# TJA1051T.net
KiCad netlist of a schematic drawn in Altium Designer
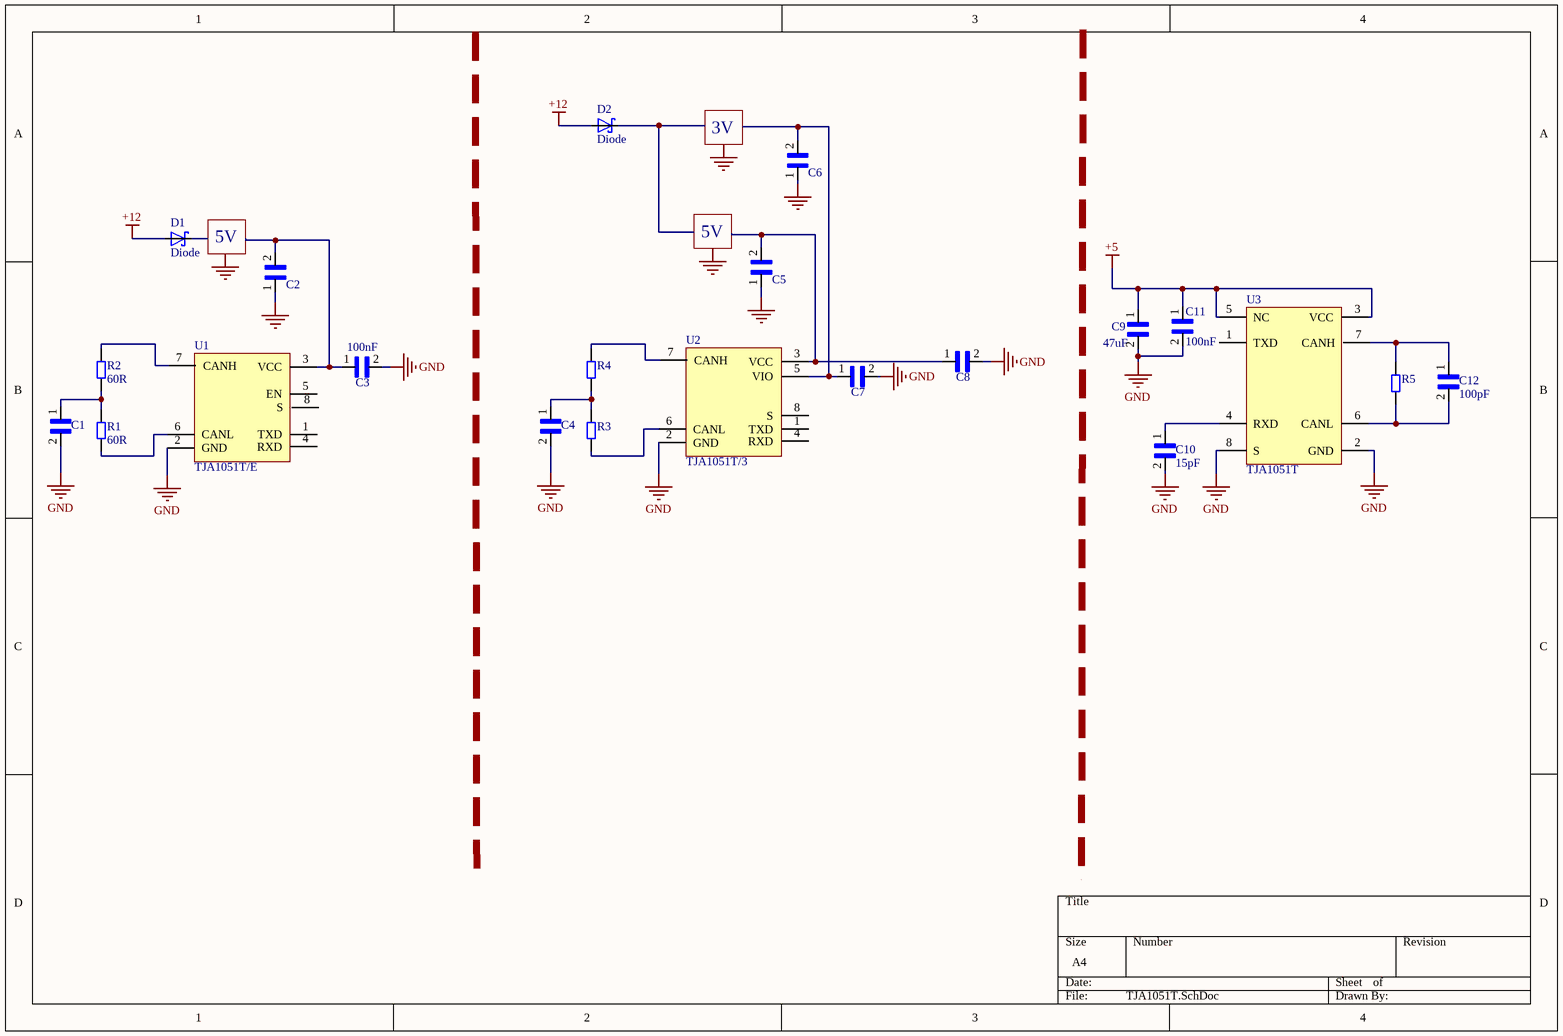
[diagram p0: TJA1051T.SchDoc]

(export (version "E")
  (design (tool "Eeschema 10.0.6"))
  (components
    (comp (ref "C1")
      (value "CAP-0805-NP0-10nF")
      (footprint "CAP-0805-NP0")
      (description "Cap Ceramic 0.01uF 50V C0G 5% Pad SMD 0805 125°C T/R")
      (fields
        (field (name "MANUFACTURER") "Yageo")
        (field (name "MANUFACTURER PART NUMBER") "CC0805JKNPO9BN103")
      )
      (libsource (lib "") (part "CAP-0805-NP0-10nF_1"))
    )
    (comp (ref "C2")
      (value "CAP-0805-NP0-10nF")
      (footprint "CAP-0805-NP0")
      (description "Cap Ceramic 0.01uF 50V C0G 5% Pad SMD 0805 125°C T/R")
      (fields
        (field (name "MANUFACTURER") "Yageo")
        (field (name "MANUFACTURER PART NUMBER") "CC0805JKNPO9BN103")
      )
      (libsource (lib "") (part "CAP-0805-NP0-10nF_2"))
    )
    (comp (ref "C3")
      (value "100nF")
      (footprint "CAP-0805-NP0")
      (description "Cap Ceramic 0.01uF 50V C0G 5% Pad SMD 0805 125°C T/R")
      (fields
        (field (name "MANUFACTURER") "Yageo")
        (field (name "MANUFACTURER PART NUMBER") "CC0805JKNPO9BN103")
      )
      (libsource (lib "Schlib2") (part "CAP-0805-NP0-10nF"))
    )
    (comp (ref "C4")
      (value "CAP-0805-NP0-10nF")
      (footprint "CAP-0805-NP0")
      (description "Cap Ceramic 0.01uF 50V C0G 5% Pad SMD 0805 125°C T/R")
      (fields
        (field (name "MANUFACTURER") "Yageo")
        (field (name "MANUFACTURER PART NUMBER") "CC0805JKNPO9BN103")
      )
      (libsource (lib "") (part "CAP-0805-NP0-10nF_1"))
    )
    (comp (ref "C5")
      (value "CAP-0805-NP0-10nF")
      (footprint "CAP-0805-NP0")
      (description "Cap Ceramic 0.01uF 50V C0G 5% Pad SMD 0805 125°C T/R")
      (fields
        (field (name "MANUFACTURER") "Yageo")
        (field (name "MANUFACTURER PART NUMBER") "CC0805JKNPO9BN103")
      )
      (libsource (lib "") (part "CAP-0805-NP0-10nF_2"))
    )
    (comp (ref "C6")
      (value "CAP-0805-NP0-10nF")
      (footprint "CAP-0805-NP0")
      (description "Cap Ceramic 0.01uF 50V C0G 5% Pad SMD 0805 125°C T/R")
      (fields
        (field (name "MANUFACTURER") "Yageo")
        (field (name "MANUFACTURER PART NUMBER") "CC0805JKNPO9BN103")
      )
      (libsource (lib "") (part "CAP-0805-NP0-10nF_2"))
    )
    (comp (ref "C7")
      (value "CAP-0805-NP0-10nF")
      (footprint "CAP-0805-NP0")
      (description "Cap Ceramic 0.01uF 50V C0G 5% Pad SMD 0805 125°C T/R")
      (fields
        (field (name "MANUFACTURER") "Yageo")
        (field (name "MANUFACTURER PART NUMBER") "CC0805JKNPO9BN103")
      )
      (libsource (lib "Schlib2") (part "CAP-0805-NP0-10nF"))
    )
    (comp (ref "C8")
      (value "CAP-0805-NP0-10nF")
      (footprint "CAP-0805-NP0")
      (description "Cap Ceramic 0.01uF 50V C0G 5% Pad SMD 0805 125°C T/R")
      (fields
        (field (name "MANUFACTURER") "Yageo")
        (field (name "MANUFACTURER PART NUMBER") "CC0805JKNPO9BN103")
      )
      (libsource (lib "Schlib2") (part "CAP-0805-NP0-10nF"))
    )
    (comp (ref "C9")
      (value "47uF")
      (footprint "CAP-0805-NP0")
      (description "Cap Ceramic 0.01uF 50V C0G 5% Pad SMD 0805 125°C T/R")
      (fields
        (field (name "MANUFACTURER") "Yageo")
        (field (name "MANUFACTURER PART NUMBER") "CC0805JKNPO9BN103")
      )
      (libsource (lib "") (part "CAP-0805-NP0-10nF_1"))
    )
    (comp (ref "C10")
      (value "15pF")
      (footprint "CAP-0805-NP0")
      (description "Cap Ceramic 0.01uF 50V C0G 5% Pad SMD 0805 125°C T/R")
      (fields
        (field (name "MANUFACTURER") "Yageo")
        (field (name "MANUFACTURER PART NUMBER") "CC0805JKNPO9BN103")
      )
      (libsource (lib "") (part "CAP-0805-NP0-10nF_1"))
    )
    (comp (ref "C11")
      (value "100nF")
      (footprint "CAP-0805-NP0")
      (description "Cap Ceramic 0.01uF 50V C0G 5% Pad SMD 0805 125°C T/R")
      (fields
        (field (name "MANUFACTURER") "Yageo")
        (field (name "MANUFACTURER PART NUMBER") "CC0805JKNPO9BN103")
      )
      (libsource (lib "") (part "CAP-0805-NP0-10nF_1"))
    )
    (comp (ref "C12")
      (value "100pF")
      (footprint "CAP-0805-NP0")
      (description "Cap Ceramic 0.01uF 50V C0G 5% Pad SMD 0805 125°C T/R")
      (fields
        (field (name "MANUFACTURER") "Yageo")
        (field (name "MANUFACTURER PART NUMBER") "CC0805JKNPO9BN103")
      )
      (libsource (lib "") (part "CAP-0805-NP0-10nF_1"))
    )
    (comp (ref "D1") (value "Diode") (footprint "Diode") (libsource (lib "Schlib1") (part "Diode")))
    (comp (ref "D2") (value "Diode") (footprint "Diode") (libsource (lib "") (part "Diode_1")))
    (comp (ref "R1")
      (value "60R")
      (footprint "RES-0805")
      (description "Res SMD 0805 10K 1% 0.125W T.C.100PPM")
      (fields
        (field (name "MANUFACTURER") "Yageo")
        (field (name "MANUFACTURER PART NUMBER") "RC0805FR-0710KL")
      )
      (libsource (lib "Schlib2") (part "RES-0805-10k"))
    )
    (comp (ref "R2")
      (value "60R")
      (footprint "RES-0805")
      (description "Res SMD 0805 10K 1% 0.125W T.C.100PPM")
      (fields
        (field (name "MANUFACTURER") "Yageo")
        (field (name "MANUFACTURER PART NUMBER") "RC0805FR-0710KL")
      )
      (libsource (lib "Schlib2") (part "RES-0805-10k"))
    )
    (comp (ref "R3")
      (value "RES-0805-10k")
      (footprint "RES-0805")
      (description "Res SMD 0805 10K 1% 0.125W T.C.100PPM")
      (fields
        (field (name "MANUFACTURER") "Yageo")
        (field (name "MANUFACTURER PART NUMBER") "RC0805FR-0710KL")
      )
      (libsource (lib "Schlib2") (part "RES-0805-10k"))
    )
    (comp (ref "R4")
      (value "RES-0805-10k")
      (footprint "RES-0805")
      (description "Res SMD 0805 10K 1% 0.125W T.C.100PPM")
      (fields
        (field (name "MANUFACTURER") "Yageo")
        (field (name "MANUFACTURER PART NUMBER") "RC0805FR-0710KL")
      )
      (libsource (lib "Schlib2") (part "RES-0805-10k"))
    )
    (comp (ref "R5")
      (value "120R")
      (footprint "RES-0805")
      (description "Res SMD 0805 10K 1% 0.125W T.C.100PPM")
      (fields
        (field (name "MANUFACTURER") "Yageo")
        (field (name "MANUFACTURER PART NUMBER") "RC0805FR-0710KL")
      )
      (libsource (lib "Schlib2") (part "RES-0805-10k"))
    )
    (comp (ref "U1")
      (value "TJA1051T/E")
      (footprint "TJA1051T")
      (description "TJA1051 Series 5.5 V Surface Mount High-Speed CAN Transceiver - SOIC-8")
      (fields
        (field (name "MANUFACTURER") "NXP Semiconductors")
        (field (name "MANUFACTURER PART NUMBER") "TJA1051T/E,118")
      )
      (libsource (lib "Schlib1") (part "TJA1051T/E"))
    )
    (comp (ref "U2")
      (value "TJA1051T/3")
      (footprint "TJA1051T")
      (description "TJA1051 Single 5 V 1 MBd Surface Mount High Speed CAN Transceiver - HVSON-8")
      (fields
        (field (name "MANUFACTURER") "NXP Semiconductors")
        (field (name "MANUFACTURER PART NUMBER") "TJA1051TK/3/1J")
      )
      (libsource (lib "Schlib2") (part "TJA1051T/3"))
    )
    (comp (ref "U3")
      (value "TJA1051T")
      (footprint "TJA1051T")
      (description "CAN 1Mbps Normal/Silent 5V 8-Pin SO Tube")
      (fields (field (name "MANUFACTURER") "NXP Semiconductors"))
      (libsource (lib "Schlib2") (part "TJA1051T"))
    )
  )
  (nets
    (net (code "1") (name "+5") (class "Default")
      (node (ref "C11") (pin "1") (pinfunction "1_1") (pintype "passive"))
      (node (ref "C9") (pin "1") (pinfunction "1_1") (pintype "passive"))
      (node (ref "U3") (pin "3") (pinfunction "VCC_3") (pintype "passive"))
      (node (ref "U3") (pin "5") (pinfunction "NC_5") (pintype "power_in"))
    )
    (net (code "2") (name "+12") (class "Default")
      (node (ref "D1") (pin "1") (pintype "passive"))
      (node (ref "D2") (pin "2") (pintype "passive"))
    )
    (net (code "3") (name "GND") (class "Default")
      (node (ref "C1") (pin "2") (pinfunction "2_2") (pintype "passive"))
      (node (ref "C10") (pin "2") (pinfunction "2_2") (pintype "passive"))
      (node (ref "C11") (pin "2") (pinfunction "2_2") (pintype "passive"))
      (node (ref "C2") (pin "1") (pinfunction "1_1") (pintype "passive"))
      (node (ref "C3") (pin "2") (pinfunction "2_2") (pintype "passive"))
      (node (ref "C4") (pin "2") (pinfunction "2_2") (pintype "passive"))
      (node (ref "C5") (pin "1") (pinfunction "1_1") (pintype "passive"))
      (node (ref "C6") (pin "1") (pinfunction "1_1") (pintype "passive"))
      (node (ref "C7") (pin "2") (pinfunction "2_2") (pintype "passive"))
      (node (ref "C8") (pin "2") (pinfunction "2_2") (pintype "passive"))
      (node (ref "C9") (pin "2") (pinfunction "2_2") (pintype "passive"))
      (node (ref "U1") (pin "2") (pinfunction "GND_2") (pintype "passive"))
      (node (ref "U2") (pin "2") (pinfunction "GND_2") (pintype "passive"))
      (node (ref "U3") (pin "2") (pinfunction "GND_2") (pintype "passive"))
      (node (ref "U3") (pin "8") (pinfunction "S_8") (pintype "passive"))
    )
    (net (code "4") (name "Net-(C1-Pad1)") (class "Default")
      (node (ref "C1") (pin "1") (pinfunction "1_1") (pintype "passive"))
      (node (ref "R1") (pin "2") (pinfunction "2_2") (pintype "passive"))
      (node (ref "R2") (pin "1") (pinfunction "1_1") (pintype "passive"))
    )
    (net (code "5") (name "Net-(C4-Pad1)") (class "Default")
      (node (ref "C4") (pin "1") (pinfunction "1_1") (pintype "passive"))
      (node (ref "R3") (pin "2") (pinfunction "2_2") (pintype "passive"))
      (node (ref "R4") (pin "1") (pinfunction "1_1") (pintype "passive"))
    )
    (net (code "6") (name "Net-(U1-CANH)") (class "Default")
      (node (ref "R2") (pin "2") (pinfunction "2_2") (pintype "passive"))
      (node (ref "U1") (pin "7") (pinfunction "CANH_7") (pintype "passive"))
    )
    (net (code "7") (name "Net-(U1-CANL)") (class "Default")
      (node (ref "R1") (pin "1") (pinfunction "1_1") (pintype "passive"))
      (node (ref "U1") (pin "6") (pinfunction "CANL_6") (pintype "passive"))
    )
    (net (code "8") (name "Net-(U1-VCC)") (class "Default")
      (node (ref "C2") (pin "2") (pinfunction "2_2") (pintype "passive"))
      (node (ref "C3") (pin "1") (pinfunction "1_1") (pintype "passive"))
      (node (ref "U1") (pin "3") (pinfunction "VCC_3") (pintype "passive"))
    )
    (net (code "9") (name "Net-(U2-CANH)") (class "Default")
      (node (ref "R4") (pin "2") (pinfunction "2_2") (pintype "passive"))
      (node (ref "U2") (pin "7") (pinfunction "CANH_7") (pintype "passive"))
    )
    (net (code "10") (name "Net-(U2-CANL)") (class "Default")
      (node (ref "R3") (pin "1") (pinfunction "1_1") (pintype "passive"))
      (node (ref "U2") (pin "6") (pinfunction "CANL_6") (pintype "passive"))
    )
    (net (code "11") (name "Net-(U2-VCC)") (class "Default")
      (node (ref "C5") (pin "2") (pinfunction "2_2") (pintype "passive"))
      (node (ref "C8") (pin "1") (pinfunction "1_1") (pintype "passive"))
      (node (ref "U2") (pin "3") (pinfunction "VCC_3") (pintype "passive"))
    )
    (net (code "12") (name "Net-(U2-VIO)") (class "Default")
      (node (ref "C6") (pin "2") (pinfunction "2_2") (pintype "passive"))
      (node (ref "C7") (pin "1") (pinfunction "1_1") (pintype "passive"))
      (node (ref "U2") (pin "5") (pinfunction "VIO_5") (pintype "power_in"))
    )
    (net (code "13") (name "Net-(U3-CANH)") (class "Default")
      (node (ref "C12") (pin "1") (pinfunction "1_1") (pintype "passive"))
      (node (ref "R5") (pin "2") (pinfunction "2_2") (pintype "passive"))
      (node (ref "U3") (pin "7") (pinfunction "CANH_7") (pintype "passive"))
    )
    (net (code "14") (name "Net-(U3-CANL)") (class "Default")
      (node (ref "C12") (pin "2") (pinfunction "2_2") (pintype "passive"))
      (node (ref "R5") (pin "1") (pinfunction "1_1") (pintype "passive"))
      (node (ref "U3") (pin "6") (pinfunction "CANL_6") (pintype "passive"))
    )
    (net (code "15") (name "Net-(U3-RXD)") (class "Default")
      (node (ref "C10") (pin "1") (pinfunction "1_1") (pintype "passive"))
      (node (ref "U3") (pin "4") (pinfunction "RXD_4") (pintype "passive"))
    )
    (net (code "16") (name "unconnected-(D1-Pad2)") (class "Default")
      (node (ref "D1") (pin "2") (pintype "passive"))
    )
    (net (code "17") (name "unconnected-(D2-Pad1)") (class "Default")
      (node (ref "D2") (pin "1") (pintype "passive"))
    )
    (net (code "18") (name "unconnected-(U1-EN-Pad5)") (class "Default")
      (node (ref "U1") (pin "5") (pinfunction "EN_5") (pintype "power_in"))
    )
    (net (code "19") (name "unconnected-(U1-RXD-Pad4)") (class "Default")
      (node (ref "U1") (pin "4") (pinfunction "RXD_4") (pintype "passive"))
    )
    (net (code "20") (name "unconnected-(U1-S-Pad8)") (class "Default")
      (node (ref "U1") (pin "8") (pinfunction "S_8") (pintype "passive"))
    )
    (net (code "21") (name "unconnected-(U1-TXD-Pad1)") (class "Default")
      (node (ref "U1") (pin "1") (pinfunction "TXD_1") (pintype "passive"))
    )
    (net (code "22") (name "unconnected-(U2-RXD-Pad4)") (class "Default")
      (node (ref "U2") (pin "4") (pinfunction "RXD_4") (pintype "passive"))
    )
    (net (code "23") (name "unconnected-(U2-S-Pad8)") (class "Default")
      (node (ref "U2") (pin "8") (pinfunction "S_8") (pintype "passive"))
    )
    (net (code "24") (name "unconnected-(U2-TXD-Pad1)") (class "Default")
      (node (ref "U2") (pin "1") (pinfunction "TXD_1") (pintype "passive"))
    )
    (net (code "25") (name "unconnected-(U3-TXD-Pad1)") (class "Default")
      (node (ref "U3") (pin "1") (pinfunction "TXD_1") (pintype "passive"))
    )
  )
)
